# 14-DPLL-03.net
KiCad netlist of a schematic drawn in Altium Designer
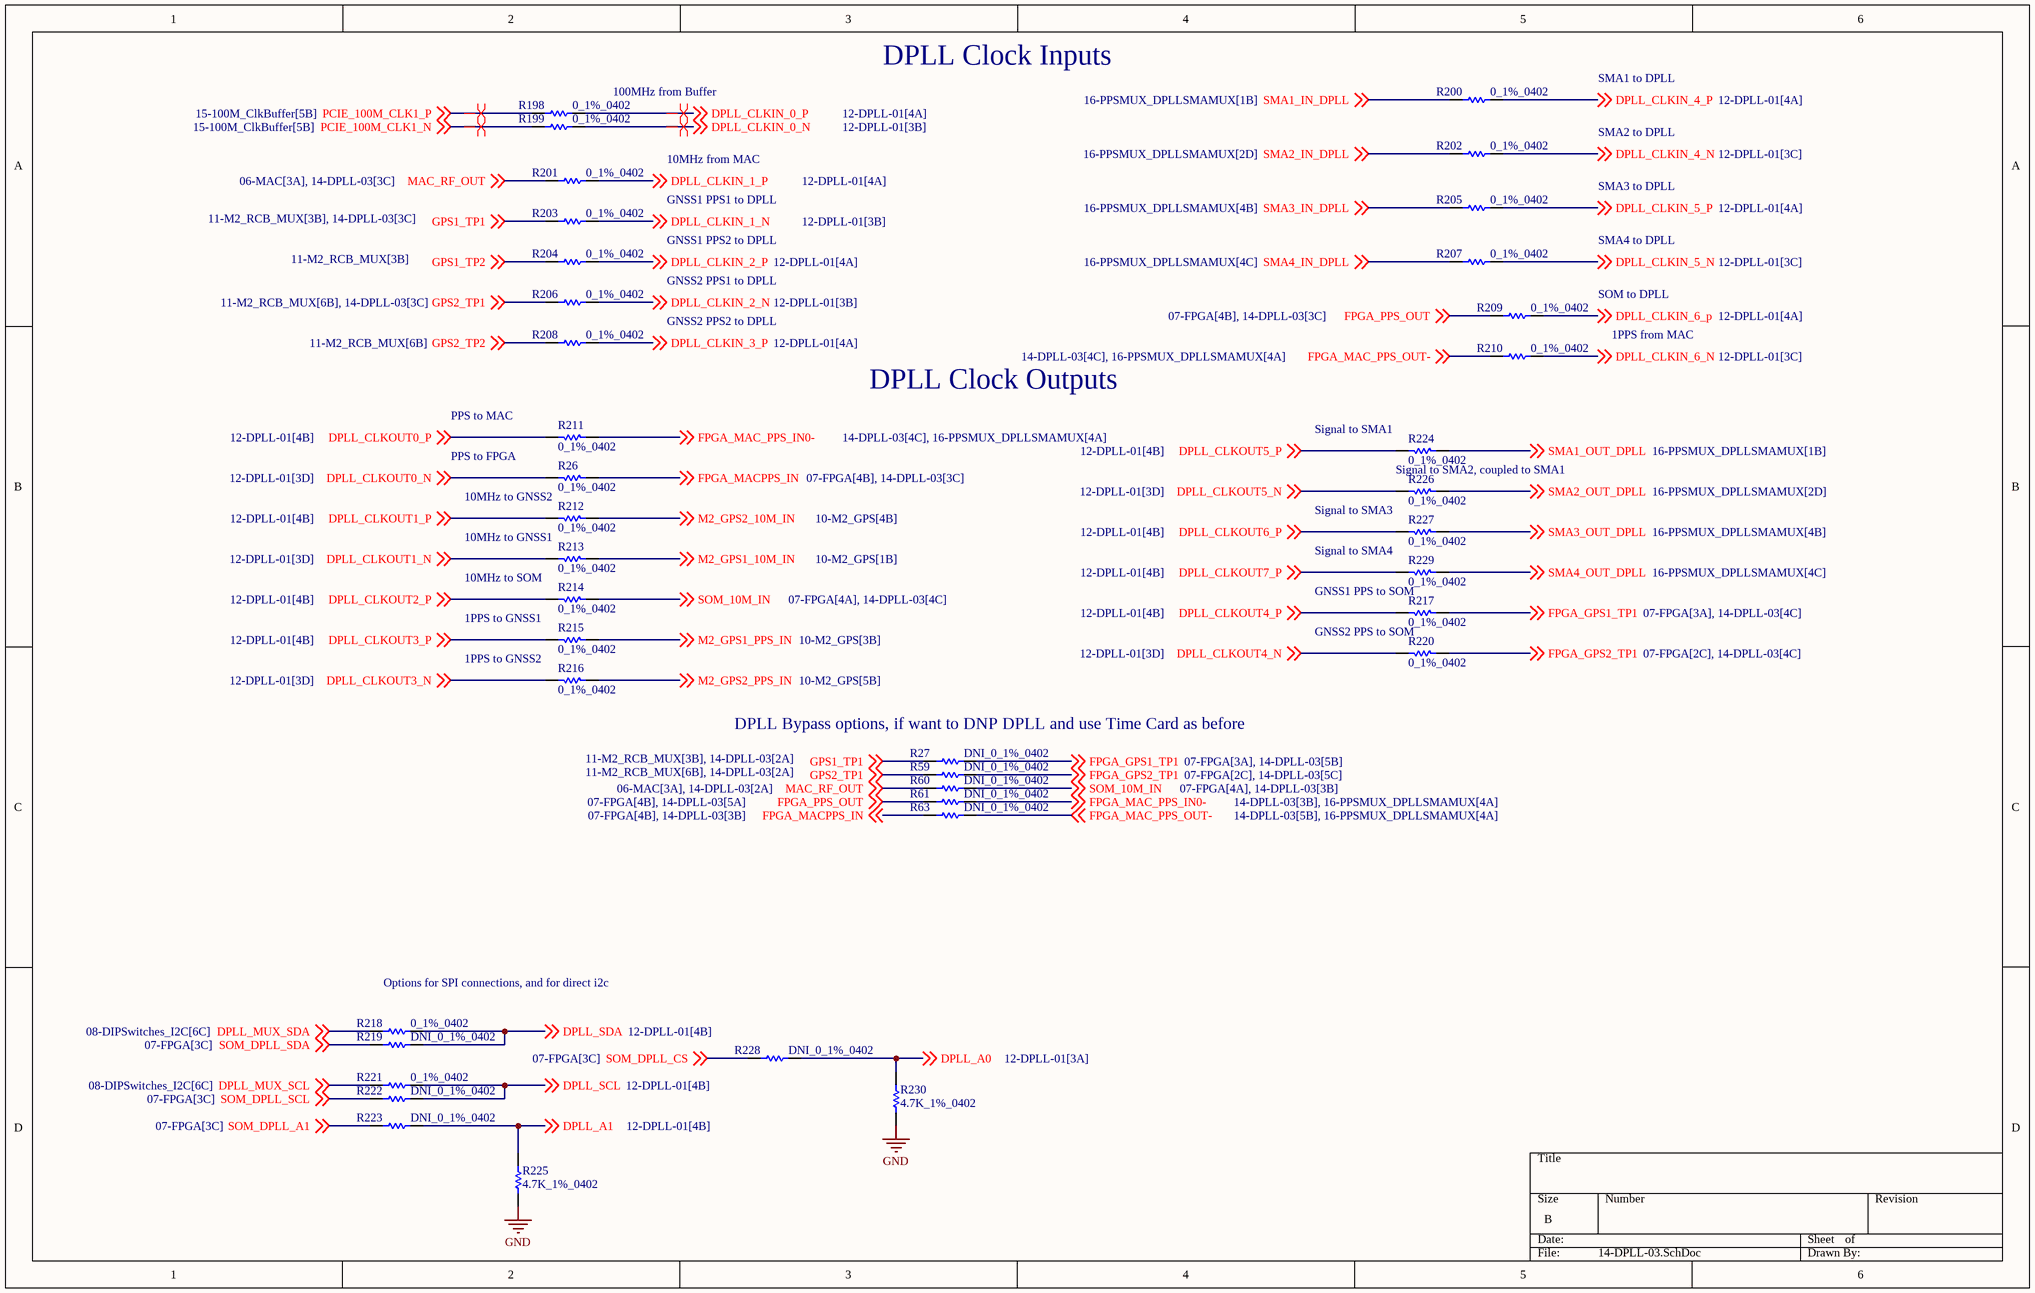
[diagram p0: 14-DPLL-03.SchDoc]

(export (version "E")
  (design (tool "Eeschema 10.0.6"))
  (components
    (comp (ref "R26")
      (value "0_1%_0402")
      (footprint "RESC1005X40X25LL05T05")
      (description "Chip Resistor, 0 Ohm, 0.1 W, -55 to 155 degC, 0402 (1005 Metric), RoHS, Tape and Reel")
      (fields (field (name "MANUFACTURER") "Panasonic") (field (name "TOLERANCE") "5%"))
      (libsource (lib "Altium Content Vault") (part "RES-2"))
    )
    (comp (ref "R27")
      (value "DNI_0_1%_0402")
      (footprint "RESC1005X40X25LL05T05")
      (description "Chip Resistor, 0 Ohm, 0.1 W, -55 to 155 degC, 0402 (1005 Metric), RoHS, Tape and Reel")
      (fields (field (name "MANUFACTURER") "Panasonic") (field (name "TOLERANCE") "5%"))
      (libsource (lib "Altium Content Vault") (part "RES-2"))
    )
    (comp (ref "R59")
      (value "DNI_0_1%_0402")
      (footprint "RESC1005X40X25LL05T05")
      (description "Chip Resistor, 0 Ohm, 0.1 W, -55 to 155 degC, 0402 (1005 Metric), RoHS, Tape and Reel")
      (fields (field (name "MANUFACTURER") "Panasonic") (field (name "TOLERANCE") "5%"))
      (libsource (lib "Altium Content Vault") (part "RES-2"))
    )
    (comp (ref "R60")
      (value "DNI_0_1%_0402")
      (footprint "RESC1005X40X25LL05T05")
      (description "Chip Resistor, 0 Ohm, 0.1 W, -55 to 155 degC, 0402 (1005 Metric), RoHS, Tape and Reel")
      (fields (field (name "MANUFACTURER") "Panasonic") (field (name "TOLERANCE") "5%"))
      (libsource (lib "Altium Content Vault") (part "RES-2"))
    )
    (comp (ref "R61")
      (value "DNI_0_1%_0402")
      (footprint "RESC1005X40X25LL05T05")
      (description "Chip Resistor, 0 Ohm, 0.1 W, -55 to 155 degC, 0402 (1005 Metric), RoHS, Tape and Reel")
      (fields (field (name "MANUFACTURER") "Panasonic") (field (name "TOLERANCE") "5%"))
      (libsource (lib "Altium Content Vault") (part "RES-2"))
    )
    (comp (ref "R63")
      (value "DNI_0_1%_0402")
      (footprint "RESC1005X40X25LL05T05")
      (description "Chip Resistor, 0 Ohm, 0.1 W, -55 to 155 degC, 0402 (1005 Metric), RoHS, Tape and Reel")
      (fields (field (name "MANUFACTURER") "Panasonic") (field (name "TOLERANCE") "5%"))
      (libsource (lib "Altium Content Vault") (part "RES-2"))
    )
    (comp (ref "R198")
      (value "0_1%_0402")
      (footprint "RESC1005X40X25LL05T05")
      (description "Chip Resistor, 0 Ohm, 0.1 W, -55 to 155 degC, 0402 (1005 Metric), RoHS, Tape and Reel")
      (fields (field (name "MANUFACTURER") "Panasonic") (field (name "TOLERANCE") "5%"))
      (libsource (lib "Altium Content Vault") (part "RES-2"))
    )
    (comp (ref "R199")
      (value "0_1%_0402")
      (footprint "RESC1005X40X25LL05T05")
      (description "Chip Resistor, 0 Ohm, 0.1 W, -55 to 155 degC, 0402 (1005 Metric), RoHS, Tape and Reel")
      (fields (field (name "MANUFACTURER") "Panasonic") (field (name "TOLERANCE") "5%"))
      (libsource (lib "Altium Content Vault") (part "RES-2"))
    )
    (comp (ref "R200")
      (value "0_1%_0402")
      (footprint "RESC1005X40X25LL05T05")
      (description "Chip Resistor, 0 Ohm, 0.1 W, -55 to 155 degC, 0402 (1005 Metric), RoHS, Tape and Reel")
      (fields (field (name "MANUFACTURER") "Panasonic") (field (name "TOLERANCE") "5%"))
      (libsource (lib "Altium Content Vault") (part "RES-2"))
    )
    (comp (ref "R201")
      (value "0_1%_0402")
      (footprint "RESC1005X40X25LL05T05")
      (description "Chip Resistor, 0 Ohm, 0.1 W, -55 to 155 degC, 0402 (1005 Metric), RoHS, Tape and Reel")
      (fields (field (name "MANUFACTURER") "Panasonic") (field (name "TOLERANCE") "5%"))
      (libsource (lib "Altium Content Vault") (part "RES-2"))
    )
    (comp (ref "R202")
      (value "0_1%_0402")
      (footprint "RESC1005X40X25LL05T05")
      (description "Chip Resistor, 0 Ohm, 0.1 W, -55 to 155 degC, 0402 (1005 Metric), RoHS, Tape and Reel")
      (fields (field (name "MANUFACTURER") "Panasonic") (field (name "TOLERANCE") "5%"))
      (libsource (lib "Altium Content Vault") (part "RES-2"))
    )
    (comp (ref "R203")
      (value "0_1%_0402")
      (footprint "RESC1005X40X25LL05T05")
      (description "Chip Resistor, 0 Ohm, 0.1 W, -55 to 155 degC, 0402 (1005 Metric), RoHS, Tape and Reel")
      (fields (field (name "MANUFACTURER") "Panasonic") (field (name "TOLERANCE") "5%"))
      (libsource (lib "Altium Content Vault") (part "RES-2"))
    )
    (comp (ref "R204")
      (value "0_1%_0402")
      (footprint "RESC1005X40X25LL05T05")
      (description "Chip Resistor, 0 Ohm, 0.1 W, -55 to 155 degC, 0402 (1005 Metric), RoHS, Tape and Reel")
      (fields (field (name "MANUFACTURER") "Panasonic") (field (name "TOLERANCE") "5%"))
      (libsource (lib "Altium Content Vault") (part "RES-2"))
    )
    (comp (ref "R205")
      (value "0_1%_0402")
      (footprint "RESC1005X40X25LL05T05")
      (description "Chip Resistor, 0 Ohm, 0.1 W, -55 to 155 degC, 0402 (1005 Metric), RoHS, Tape and Reel")
      (fields (field (name "MANUFACTURER") "Panasonic") (field (name "TOLERANCE") "5%"))
      (libsource (lib "Altium Content Vault") (part "RES-2"))
    )
    (comp (ref "R206")
      (value "0_1%_0402")
      (footprint "RESC1005X40X25LL05T05")
      (description "Chip Resistor, 0 Ohm, 0.1 W, -55 to 155 degC, 0402 (1005 Metric), RoHS, Tape and Reel")
      (fields (field (name "MANUFACTURER") "Panasonic") (field (name "TOLERANCE") "5%"))
      (libsource (lib "Altium Content Vault") (part "RES-2"))
    )
    (comp (ref "R207")
      (value "0_1%_0402")
      (footprint "RESC1005X40X25LL05T05")
      (description "Chip Resistor, 0 Ohm, 0.1 W, -55 to 155 degC, 0402 (1005 Metric), RoHS, Tape and Reel")
      (fields (field (name "MANUFACTURER") "Panasonic") (field (name "TOLERANCE") "5%"))
      (libsource (lib "Altium Content Vault") (part "RES-2"))
    )
    (comp (ref "R208")
      (value "0_1%_0402")
      (footprint "RESC1005X40X25LL05T05")
      (description "Chip Resistor, 0 Ohm, 0.1 W, -55 to 155 degC, 0402 (1005 Metric), RoHS, Tape and Reel")
      (fields (field (name "MANUFACTURER") "Panasonic") (field (name "TOLERANCE") "5%"))
      (libsource (lib "Altium Content Vault") (part "RES-2"))
    )
    (comp (ref "R209")
      (value "0_1%_0402")
      (footprint "RESC1005X40X25LL05T05")
      (description "Chip Resistor, 0 Ohm, 0.1 W, -55 to 155 degC, 0402 (1005 Metric), RoHS, Tape and Reel")
      (fields (field (name "MANUFACTURER") "Panasonic") (field (name "TOLERANCE") "5%"))
      (libsource (lib "Altium Content Vault") (part "RES-2"))
    )
    (comp (ref "R210")
      (value "0_1%_0402")
      (footprint "RESC1005X40X25LL05T05")
      (description "Chip Resistor, 0 Ohm, 0.1 W, -55 to 155 degC, 0402 (1005 Metric), RoHS, Tape and Reel")
      (fields (field (name "MANUFACTURER") "Panasonic") (field (name "TOLERANCE") "5%"))
      (libsource (lib "Altium Content Vault") (part "RES-2"))
    )
    (comp (ref "R211")
      (value "0_1%_0402")
      (footprint "RESC1005X40X25LL05T05")
      (description "Chip Resistor, 0 Ohm, 0.1 W, -55 to 155 degC, 0402 (1005 Metric), RoHS, Tape and Reel")
      (fields (field (name "MANUFACTURER") "Panasonic") (field (name "TOLERANCE") "5%"))
      (libsource (lib "Altium Content Vault") (part "RES-2"))
    )
    (comp (ref "R212")
      (value "0_1%_0402")
      (footprint "RESC1005X40X25LL05T05")
      (description "Chip Resistor, 0 Ohm, 0.1 W, -55 to 155 degC, 0402 (1005 Metric), RoHS, Tape and Reel")
      (fields (field (name "MANUFACTURER") "Panasonic") (field (name "TOLERANCE") "5%"))
      (libsource (lib "Altium Content Vault") (part "RES-2"))
    )
    (comp (ref "R213")
      (value "0_1%_0402")
      (footprint "RESC1005X40X25LL05T05")
      (description "Chip Resistor, 0 Ohm, 0.1 W, -55 to 155 degC, 0402 (1005 Metric), RoHS, Tape and Reel")
      (fields (field (name "MANUFACTURER") "Panasonic") (field (name "TOLERANCE") "5%"))
      (libsource (lib "Altium Content Vault") (part "RES-2"))
    )
    (comp (ref "R214")
      (value "0_1%_0402")
      (footprint "RESC1005X40X25LL05T05")
      (description "Chip Resistor, 0 Ohm, 0.1 W, -55 to 155 degC, 0402 (1005 Metric), RoHS, Tape and Reel")
      (fields (field (name "MANUFACTURER") "Panasonic") (field (name "TOLERANCE") "5%"))
      (libsource (lib "Altium Content Vault") (part "RES-2"))
    )
    (comp (ref "R215")
      (value "0_1%_0402")
      (footprint "RESC1005X40X25LL05T05")
      (description "Chip Resistor, 0 Ohm, 0.1 W, -55 to 155 degC, 0402 (1005 Metric), RoHS, Tape and Reel")
      (fields (field (name "MANUFACTURER") "Panasonic") (field (name "TOLERANCE") "5%"))
      (libsource (lib "Altium Content Vault") (part "RES-2"))
    )
    (comp (ref "R216")
      (value "0_1%_0402")
      (footprint "RESC1005X40X25LL05T05")
      (description "Chip Resistor, 0 Ohm, 0.1 W, -55 to 155 degC, 0402 (1005 Metric), RoHS, Tape and Reel")
      (fields (field (name "MANUFACTURER") "Panasonic") (field (name "TOLERANCE") "5%"))
      (libsource (lib "Altium Content Vault") (part "RES-2"))
    )
    (comp (ref "R217")
      (value "0_1%_0402")
      (footprint "RESC1005X40X25LL05T05")
      (description "Chip Resistor, 0 Ohm, 0.1 W, -55 to 155 degC, 0402 (1005 Metric), RoHS, Tape and Reel")
      (fields (field (name "MANUFACTURER") "Panasonic") (field (name "TOLERANCE") "5%"))
      (libsource (lib "Altium Content Vault") (part "RES-2"))
    )
    (comp (ref "R218")
      (value "0_1%_0402")
      (footprint "RESC1005X40X25LL05T05")
      (description "Chip Resistor, 0 Ohm, 0.1 W, -55 to 155 degC, 0402 (1005 Metric), RoHS, Tape and Reel")
      (fields (field (name "MANUFACTURER") "Panasonic") (field (name "TOLERANCE") "5%"))
      (libsource (lib "Altium Content Vault") (part "RES-2"))
    )
    (comp (ref "R219")
      (value "DNI_0_1%_0402")
      (footprint "RESC1005X40X25LL05T05")
      (description "Chip Resistor, 0 Ohm, 0.1 W, -55 to 155 degC, 0402 (1005 Metric), RoHS, Tape and Reel")
      (fields (field (name "MANUFACTURER") "Panasonic") (field (name "TOLERANCE") "5%"))
      (libsource (lib "Altium Content Vault") (part "RES-2"))
    )
    (comp (ref "R220")
      (value "0_1%_0402")
      (footprint "RESC1005X40X25LL05T05")
      (description "Chip Resistor, 0 Ohm, 0.1 W, -55 to 155 degC, 0402 (1005 Metric), RoHS, Tape and Reel")
      (fields (field (name "MANUFACTURER") "Panasonic") (field (name "TOLERANCE") "5%"))
      (libsource (lib "Altium Content Vault") (part "RES-2"))
    )
    (comp (ref "R221")
      (value "0_1%_0402")
      (footprint "RESC1005X40X25LL05T05")
      (description "Chip Resistor, 0 Ohm, 0.1 W, -55 to 155 degC, 0402 (1005 Metric), RoHS, Tape and Reel")
      (fields (field (name "MANUFACTURER") "Panasonic") (field (name "TOLERANCE") "5%"))
      (libsource (lib "Altium Content Vault") (part "RES-2"))
    )
    (comp (ref "R222")
      (value "DNI_0_1%_0402")
      (footprint "RESC1005X40X25LL05T05")
      (description "Chip Resistor, 0 Ohm, 0.1 W, -55 to 155 degC, 0402 (1005 Metric), RoHS, Tape and Reel")
      (fields (field (name "MANUFACTURER") "Panasonic") (field (name "TOLERANCE") "5%"))
      (libsource (lib "Altium Content Vault") (part "RES-2"))
    )
    (comp (ref "R223")
      (value "DNI_0_1%_0402")
      (footprint "RESC1005X40X25LL05T05")
      (description "Chip Resistor, 0 Ohm, 0.1 W, -55 to 155 degC, 0402 (1005 Metric), RoHS, Tape and Reel")
      (fields (field (name "MANUFACTURER") "Panasonic") (field (name "TOLERANCE") "5%"))
      (libsource (lib "Altium Content Vault") (part "RES-2"))
    )
    (comp (ref "R224")
      (value "0_1%_0402")
      (footprint "RESC1005X40X25LL05T05")
      (description "Chip Resistor, 0 Ohm, 0.1 W, -55 to 155 degC, 0402 (1005 Metric), RoHS, Tape and Reel")
      (fields (field (name "MANUFACTURER") "Panasonic") (field (name "TOLERANCE") "5%"))
      (libsource (lib "Altium Content Vault") (part "RES-2"))
    )
    (comp (ref "R225")
      (value "4.7K_1%_0402")
      (footprint "RESC1005X40X25NL10T10")
      (fields (field (name "MANUFACTURER") "Bourns") (field (name "PART NUMBER") "CR0402-FX-4701GLF"))
      (libsource (lib "Altium Content Vault") (part "RES"))
    )
    (comp (ref "R226")
      (value "0_1%_0402")
      (footprint "RESC1005X40X25LL05T05")
      (description "Chip Resistor, 0 Ohm, 0.1 W, -55 to 155 degC, 0402 (1005 Metric), RoHS, Tape and Reel")
      (fields (field (name "MANUFACTURER") "Panasonic") (field (name "TOLERANCE") "5%"))
      (libsource (lib "Altium Content Vault") (part "RES-2"))
    )
    (comp (ref "R227")
      (value "0_1%_0402")
      (footprint "RESC1005X40X25LL05T05")
      (description "Chip Resistor, 0 Ohm, 0.1 W, -55 to 155 degC, 0402 (1005 Metric), RoHS, Tape and Reel")
      (fields (field (name "MANUFACTURER") "Panasonic") (field (name "TOLERANCE") "5%"))
      (libsource (lib "Altium Content Vault") (part "RES-2"))
    )
    (comp (ref "R228")
      (value "DNI_0_1%_0402")
      (footprint "RESC1005X40X25LL05T05")
      (description "Chip Resistor, 0 Ohm, 0.1 W, -55 to 155 degC, 0402 (1005 Metric), RoHS, Tape and Reel")
      (fields (field (name "MANUFACTURER") "Panasonic") (field (name "TOLERANCE") "5%"))
      (libsource (lib "Altium Content Vault") (part "RES-2"))
    )
    (comp (ref "R229")
      (value "0_1%_0402")
      (footprint "RESC1005X40X25LL05T05")
      (description "Chip Resistor, 0 Ohm, 0.1 W, -55 to 155 degC, 0402 (1005 Metric), RoHS, Tape and Reel")
      (fields (field (name "MANUFACTURER") "Panasonic") (field (name "TOLERANCE") "5%"))
      (libsource (lib "Altium Content Vault") (part "RES-2"))
    )
    (comp (ref "R230")
      (value "4.7K_1%_0402")
      (footprint "RESC1005X40X25NL10T10")
      (fields (field (name "MANUFACTURER") "Bourns") (field (name "PART NUMBER") "CR0402-FX-4701GLF"))
      (libsource (lib "Altium Content Vault") (part "RES"))
    )
  )
  (nets
    (net (code "1") (name "DPLL_A0") (class "Default")
      (node (ref "R228") (pin "2") (pinfunction "2_2") (pintype "passive"))
      (node (ref "R230") (pin "2") (pinfunction "2_2") (pintype "passive"))
    )
    (net (code "2") (name "DPLL_A1") (class "Default")
      (node (ref "R223") (pin "2") (pinfunction "2_2") (pintype "passive"))
      (node (ref "R225") (pin "2") (pinfunction "2_2") (pintype "passive"))
    )
    (net (code "3") (name "DPLL_CLKIN_0_N") (class "Default")
      (node (ref "R199") (pin "2") (pinfunction "2_2") (pintype "passive"))
    )
    (net (code "4") (name "DPLL_CLKIN_0_P") (class "Default")
      (node (ref "R198") (pin "2") (pinfunction "2_2") (pintype "passive"))
    )
    (net (code "5") (name "DPLL_CLKIN_1_N") (class "Default")
      (node (ref "R203") (pin "2") (pinfunction "2_2") (pintype "passive"))
    )
    (net (code "6") (name "DPLL_CLKIN_1_P") (class "Default")
      (node (ref "R201") (pin "2") (pinfunction "2_2") (pintype "passive"))
    )
    (net (code "7") (name "DPLL_CLKIN_2_N") (class "Default")
      (node (ref "R206") (pin "2") (pinfunction "2_2") (pintype "passive"))
    )
    (net (code "8") (name "DPLL_CLKIN_2_P") (class "Default")
      (node (ref "R204") (pin "2") (pinfunction "2_2") (pintype "passive"))
    )
    (net (code "9") (name "DPLL_CLKIN_3_P") (class "Default")
      (node (ref "R208") (pin "2") (pinfunction "2_2") (pintype "passive"))
    )
    (net (code "10") (name "DPLL_CLKIN_4_N") (class "Default")
      (node (ref "R202") (pin "2") (pinfunction "2_2") (pintype "passive"))
    )
    (net (code "11") (name "DPLL_CLKIN_4_P") (class "Default")
      (node (ref "R200") (pin "2") (pinfunction "2_2") (pintype "passive"))
    )
    (net (code "12") (name "DPLL_CLKIN_5_N") (class "Default")
      (node (ref "R207") (pin "2") (pinfunction "2_2") (pintype "passive"))
    )
    (net (code "13") (name "DPLL_CLKIN_5_P") (class "Default")
      (node (ref "R205") (pin "2") (pinfunction "2_2") (pintype "passive"))
    )
    (net (code "14") (name "DPLL_CLKIN_6_N") (class "Default")
      (node (ref "R210") (pin "2") (pinfunction "2_2") (pintype "passive"))
    )
    (net (code "15") (name "DPLL_CLKIN_6_p") (class "Default")
      (node (ref "R209") (pin "2") (pinfunction "2_2") (pintype "passive"))
    )
    (net (code "16") (name "DPLL_CLKOUT0_N") (class "Default")
      (node (ref "R26") (pin "2") (pinfunction "2_2") (pintype "passive"))
    )
    (net (code "17") (name "DPLL_CLKOUT0_P") (class "Default")
      (node (ref "R211") (pin "2") (pinfunction "2_2") (pintype "passive"))
    )
    (net (code "18") (name "DPLL_CLKOUT1_N") (class "Default")
      (node (ref "R213") (pin "2") (pinfunction "2_2") (pintype "passive"))
    )
    (net (code "19") (name "DPLL_CLKOUT1_P") (class "Default")
      (node (ref "R212") (pin "2") (pinfunction "2_2") (pintype "passive"))
    )
    (net (code "20") (name "DPLL_CLKOUT2_P") (class "Default")
      (node (ref "R214") (pin "2") (pinfunction "2_2") (pintype "passive"))
    )
    (net (code "21") (name "DPLL_CLKOUT3_N") (class "Default")
      (node (ref "R216") (pin "2") (pinfunction "2_2") (pintype "passive"))
    )
    (net (code "22") (name "DPLL_CLKOUT3_P") (class "Default")
      (node (ref "R215") (pin "2") (pinfunction "2_2") (pintype "passive"))
    )
    (net (code "23") (name "DPLL_CLKOUT4_N") (class "Default")
      (node (ref "R220") (pin "2") (pinfunction "2_2") (pintype "passive"))
    )
    (net (code "24") (name "DPLL_CLKOUT4_P") (class "Default")
      (node (ref "R217") (pin "2") (pinfunction "2_2") (pintype "passive"))
    )
    (net (code "25") (name "DPLL_CLKOUT5_N") (class "Default")
      (node (ref "R226") (pin "2") (pinfunction "2_2") (pintype "passive"))
    )
    (net (code "26") (name "DPLL_CLKOUT5_P") (class "Default")
      (node (ref "R224") (pin "2") (pinfunction "2_2") (pintype "passive"))
    )
    (net (code "27") (name "DPLL_CLKOUT6_P") (class "Default")
      (node (ref "R227") (pin "2") (pinfunction "2_2") (pintype "passive"))
    )
    (net (code "28") (name "DPLL_CLKOUT7_P") (class "Default")
      (node (ref "R229") (pin "2") (pinfunction "2_2") (pintype "passive"))
    )
    (net (code "29") (name "DPLL_MUX_SCL") (class "Default")
      (node (ref "R221") (pin "1") (pinfunction "1_1") (pintype "passive"))
    )
    (net (code "30") (name "DPLL_MUX_SDA") (class "Default")
      (node (ref "R218") (pin "1") (pinfunction "1_1") (pintype "passive"))
    )
    (net (code "31") (name "DPLL_SCL") (class "Default")
      (node (ref "R221") (pin "2") (pinfunction "2_2") (pintype "passive"))
      (node (ref "R222") (pin "2") (pinfunction "2_2") (pintype "passive"))
    )
    (net (code "32") (name "DPLL_SDA") (class "Default")
      (node (ref "R218") (pin "2") (pinfunction "2_2") (pintype "passive"))
      (node (ref "R219") (pin "2") (pinfunction "2_2") (pintype "passive"))
    )
    (net (code "33") (name "FPGA_GPS1_TP1") (class "Default")
      (node (ref "R217") (pin "1") (pinfunction "1_1") (pintype "passive"))
      (node (ref "R27") (pin "2") (pinfunction "2_2") (pintype "passive"))
    )
    (net (code "34") (name "FPGA_GPS2_TP1") (class "Default")
      (node (ref "R220") (pin "1") (pinfunction "1_1") (pintype "passive"))
      (node (ref "R59") (pin "2") (pinfunction "2_2") (pintype "passive"))
    )
    (net (code "35") (name "FPGA_MACPPS_IN") (class "Default")
      (node (ref "R26") (pin "1") (pinfunction "1_1") (pintype "passive"))
      (node (ref "R63") (pin "1") (pinfunction "1_1") (pintype "passive"))
    )
    (net (code "36") (name "FPGA_MAC_PPS_IN0-") (class "Default")
      (node (ref "R211") (pin "1") (pinfunction "1_1") (pintype "passive"))
      (node (ref "R61") (pin "2") (pinfunction "2_2") (pintype "passive"))
    )
    (net (code "37") (name "FPGA_MAC_PPS_OUT-") (class "Default")
      (node (ref "R210") (pin "1") (pinfunction "1_1") (pintype "passive"))
      (node (ref "R63") (pin "2") (pinfunction "2_2") (pintype "passive"))
    )
    (net (code "38") (name "FPGA_PPS_OUT") (class "Default")
      (node (ref "R209") (pin "1") (pinfunction "1_1") (pintype "passive"))
      (node (ref "R61") (pin "1") (pinfunction "1_1") (pintype "passive"))
    )
    (net (code "39") (name "GND") (class "Default")
      (node (ref "R225") (pin "1") (pinfunction "1_1") (pintype "passive"))
      (node (ref "R230") (pin "1") (pinfunction "1_1") (pintype "passive"))
    )
    (net (code "40") (name "GPS1_TP1") (class "Default")
      (node (ref "R203") (pin "1") (pinfunction "1_1") (pintype "passive"))
      (node (ref "R27") (pin "1") (pinfunction "1_1") (pintype "passive"))
    )
    (net (code "41") (name "GPS1_TP2") (class "Default")
      (node (ref "R204") (pin "1") (pinfunction "1_1") (pintype "passive"))
    )
    (net (code "42") (name "GPS2_TP1") (class "Default")
      (node (ref "R206") (pin "1") (pinfunction "1_1") (pintype "passive"))
      (node (ref "R59") (pin "1") (pinfunction "1_1") (pintype "passive"))
    )
    (net (code "43") (name "GPS2_TP2") (class "Default")
      (node (ref "R208") (pin "1") (pinfunction "1_1") (pintype "passive"))
    )
    (net (code "44") (name "M2_GPS1_10M_IN") (class "Default")
      (node (ref "R213") (pin "1") (pinfunction "1_1") (pintype "passive"))
    )
    (net (code "45") (name "M2_GPS1_PPS_IN") (class "Default")
      (node (ref "R215") (pin "1") (pinfunction "1_1") (pintype "passive"))
    )
    (net (code "46") (name "M2_GPS2_10M_IN") (class "Default")
      (node (ref "R212") (pin "1") (pinfunction "1_1") (pintype "passive"))
    )
    (net (code "47") (name "M2_GPS2_PPS_IN") (class "Default")
      (node (ref "R216") (pin "1") (pinfunction "1_1") (pintype "passive"))
    )
    (net (code "48") (name "MAC_RF_OUT") (class "Default")
      (node (ref "R201") (pin "1") (pinfunction "1_1") (pintype "passive"))
      (node (ref "R60") (pin "1") (pinfunction "1_1") (pintype "passive"))
    )
    (net (code "49") (name "PCIE_100M_CLK1_N") (class "Default")
      (node (ref "R199") (pin "1") (pinfunction "1_1") (pintype "passive"))
    )
    (net (code "50") (name "PCIE_100M_CLK1_P") (class "Default")
      (node (ref "R198") (pin "1") (pinfunction "1_1") (pintype "passive"))
    )
    (net (code "51") (name "SMA1_IN_DPLL") (class "Default")
      (node (ref "R200") (pin "1") (pinfunction "1_1") (pintype "passive"))
    )
    (net (code "52") (name "SMA1_OUT_DPLL") (class "Default")
      (node (ref "R224") (pin "1") (pinfunction "1_1") (pintype "passive"))
    )
    (net (code "53") (name "SMA2_IN_DPLL") (class "Default")
      (node (ref "R202") (pin "1") (pinfunction "1_1") (pintype "passive"))
    )
    (net (code "54") (name "SMA2_OUT_DPLL") (class "Default")
      (node (ref "R226") (pin "1") (pinfunction "1_1") (pintype "passive"))
    )
    (net (code "55") (name "SMA3_IN_DPLL") (class "Default")
      (node (ref "R205") (pin "1") (pinfunction "1_1") (pintype "passive"))
    )
    (net (code "56") (name "SMA3_OUT_DPLL") (class "Default")
      (node (ref "R227") (pin "1") (pinfunction "1_1") (pintype "passive"))
    )
    (net (code "57") (name "SMA4_IN_DPLL") (class "Default")
      (node (ref "R207") (pin "1") (pinfunction "1_1") (pintype "passive"))
    )
    (net (code "58") (name "SMA4_OUT_DPLL") (class "Default")
      (node (ref "R229") (pin "1") (pinfunction "1_1") (pintype "passive"))
    )
    (net (code "59") (name "SOM_10M_IN") (class "Default")
      (node (ref "R214") (pin "1") (pinfunction "1_1") (pintype "passive"))
      (node (ref "R60") (pin "2") (pinfunction "2_2") (pintype "passive"))
    )
    (net (code "60") (name "SOM_DPLL_A1") (class "Default")
      (node (ref "R223") (pin "1") (pinfunction "1_1") (pintype "passive"))
    )
    (net (code "61") (name "SOM_DPLL_CS") (class "Default")
      (node (ref "R228") (pin "1") (pinfunction "1_1") (pintype "passive"))
    )
    (net (code "62") (name "SOM_DPLL_SCL") (class "Default")
      (node (ref "R222") (pin "1") (pinfunction "1_1") (pintype "passive"))
    )
    (net (code "63") (name "SOM_DPLL_SDA") (class "Default")
      (node (ref "R219") (pin "1") (pinfunction "1_1") (pintype "passive"))
    )
  )
)
